# schematic.net
KiCad netlist of a schematic drawn in EAGLE
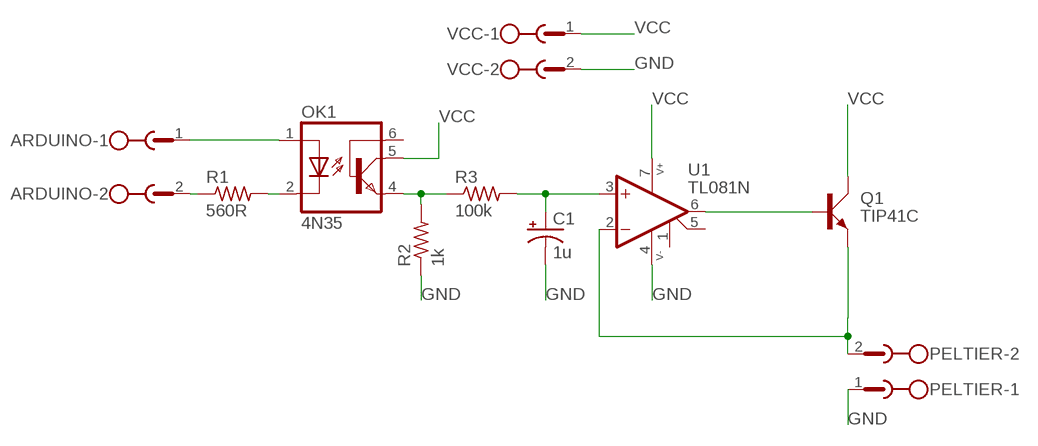
[diagram p0: schematic, sheet 1]

(export (version "E")
  (design (tool "Eeschema 10.0.6"))
  (components
    (comp (ref "ARDUINO")
      (value "MSTBV2")
      (footprint "eagle-import:MSTBV2")
      (fields (field (name "MPN") "MSTBV 2,5/2-GF-5.08"))
      (libsource (lib "eagle-import") (part "MSTBV2"))
    )
    (comp (ref "C1")
      (value "1u")
      (footprint "eagle-import:E2,5-7")
      (libsource (lib "eagle-import") (part "CPOL-USE2.5-7"))
    )
    (comp (ref "OK1")
      (value "4N35")
      (footprint "eagle-import:DIL06")
      (fields (field (name "MF") "FAIRCHILD SEMICONDUCTOR"))
      (libsource (lib "eagle-import") (part "4N35"))
    )
    (comp (ref "PELTIER")
      (value "MST2V")
      (footprint "eagle-import:MSTBV2")
      (libsource (lib "eagle-import") (part "MST2V"))
    )
    (comp (ref "Q1")
      (value "TIP41C")
      (footprint "eagle-import:TO220AV")
      (libsource (lib "eagle-import") (part "TIP41C"))
    )
    (comp (ref "R1")
      (value "560R")
      (footprint "eagle-import:0207_10")
      (libsource (lib "eagle-import") (part "R-US_0207/10"))
    )
    (comp (ref "R2")
      (value "1k")
      (footprint "eagle-import:0207_10")
      (libsource (lib "eagle-import") (part "R-US_0207/10"))
    )
    (comp (ref "R3")
      (value "100k")
      (footprint "eagle-import:0207_10")
      (libsource (lib "eagle-import") (part "R-US_0207/10"))
    )
    (comp (ref "U1")
      (value "TL081N")
      (footprint "eagle-import:DIL08")
      (libsource (lib "eagle-import") (part "TL081N"))
    )
    (comp (ref "VCC")
      (value "MSTBV2")
      (footprint "eagle-import:MSTBV2")
      (fields (field (name "MPN") "MSTBV 2,5/2-GF-5.08"))
      (libsource (lib "eagle-import") (part "MSTBV2"))
    )
  )
  (nets
    (net (code "1") (name "/GND") (class "Default")
      (node (ref "C1") (pin "-") (pinfunction "-_-") (pintype "passive"))
      (node (ref "PELTIER") (pin "1") (pinfunction "1_1") (pintype "passive"))
      (node (ref "R2") (pin "1") (pinfunction "1_1") (pintype "passive"))
      (node (ref "U1") (pin "4") (pinfunction "V-_4") (pintype "power_in"))
      (node (ref "VCC") (pin "2") (pinfunction "1_2") (pintype "passive"))
    )
    (net (code "2") (name "/VCC") (class "Default")
      (node (ref "OK1") (pin "5") (pinfunction "COL_5") (pintype "passive"))
      (node (ref "Q1") (pin "C") (pinfunction "C_C") (pintype "passive"))
      (node (ref "U1") (pin "7") (pinfunction "V+_7") (pintype "power_in"))
      (node (ref "VCC") (pin "1") (pinfunction "1_1") (pintype "passive"))
    )
    (net (code "3") (name "Net-(ARDUINOB-1)") (class "Default")
      (node (ref "ARDUINO") (pin "2") (pinfunction "1_2") (pintype "passive"))
      (node (ref "R1") (pin "1") (pinfunction "1_1") (pintype "passive"))
    )
    (net (code "4") (name "Net-(OK1-A)") (class "Default")
      (node (ref "ARDUINO") (pin "1") (pinfunction "1_1") (pintype "passive"))
      (node (ref "OK1") (pin "1") (pinfunction "A_1") (pintype "passive"))
    )
    (net (code "5") (name "Net-(OK1-C)") (class "Default")
      (node (ref "OK1") (pin "2") (pinfunction "C_2") (pintype "passive"))
      (node (ref "R1") (pin "2") (pinfunction "2_2") (pintype "passive"))
    )
    (net (code "6") (name "Net-(OK1-EMI)") (class "Default")
      (node (ref "OK1") (pin "4") (pinfunction "EMI_4") (pintype "passive"))
      (node (ref "R2") (pin "2") (pinfunction "2_2") (pintype "passive"))
      (node (ref "R3") (pin "1") (pinfunction "1_1") (pintype "passive"))
    )
    (net (code "7") (name "Net-(PELTIERB-1)") (class "Default")
      (node (ref "PELTIER") (pin "2") (pinfunction "1_2") (pintype "passive"))
      (node (ref "Q1") (pin "E") (pinfunction "E_E") (pintype "passive"))
      (node (ref "U1") (pin "2") (pinfunction "-IN_2") (pintype "input"))
    )
    (net (code "8") (name "Net-(U1B-+IN)") (class "Default")
      (node (ref "C1") (pin "+") (pinfunction "+_+") (pintype "passive"))
      (node (ref "R3") (pin "2") (pinfunction "2_2") (pintype "passive"))
      (node (ref "U1") (pin "3") (pinfunction "+IN_3") (pintype "input"))
    )
    (net (code "9") (name "Net-(U1B-OUT)") (class "Default")
      (node (ref "Q1") (pin "B") (pinfunction "B_B") (pintype "passive"))
      (node (ref "U1") (pin "6") (pinfunction "OUT_6") (pintype "output"))
    )
    (net (code "10") (name "unconnected-(OK1-BAS-Pad6)") (class "Default")
      (node (ref "OK1") (pin "6") (pinfunction "BAS_6") (pintype "passive"))
    )
    (net (code "11") (name "unconnected-(U1A-NULL1-Pad1)") (class "Default")
      (node (ref "U1") (pin "1") (pinfunction "NULL1_1") (pintype "passive"))
    )
    (net (code "12") (name "unconnected-(U1A-NULL2-Pad5)") (class "Default")
      (node (ref "U1") (pin "5") (pinfunction "NULL2_5") (pintype "passive"))
    )
  )
)
